# DXProMiniBoard.net
KiCad netlist of a schematic drawn in EAGLE
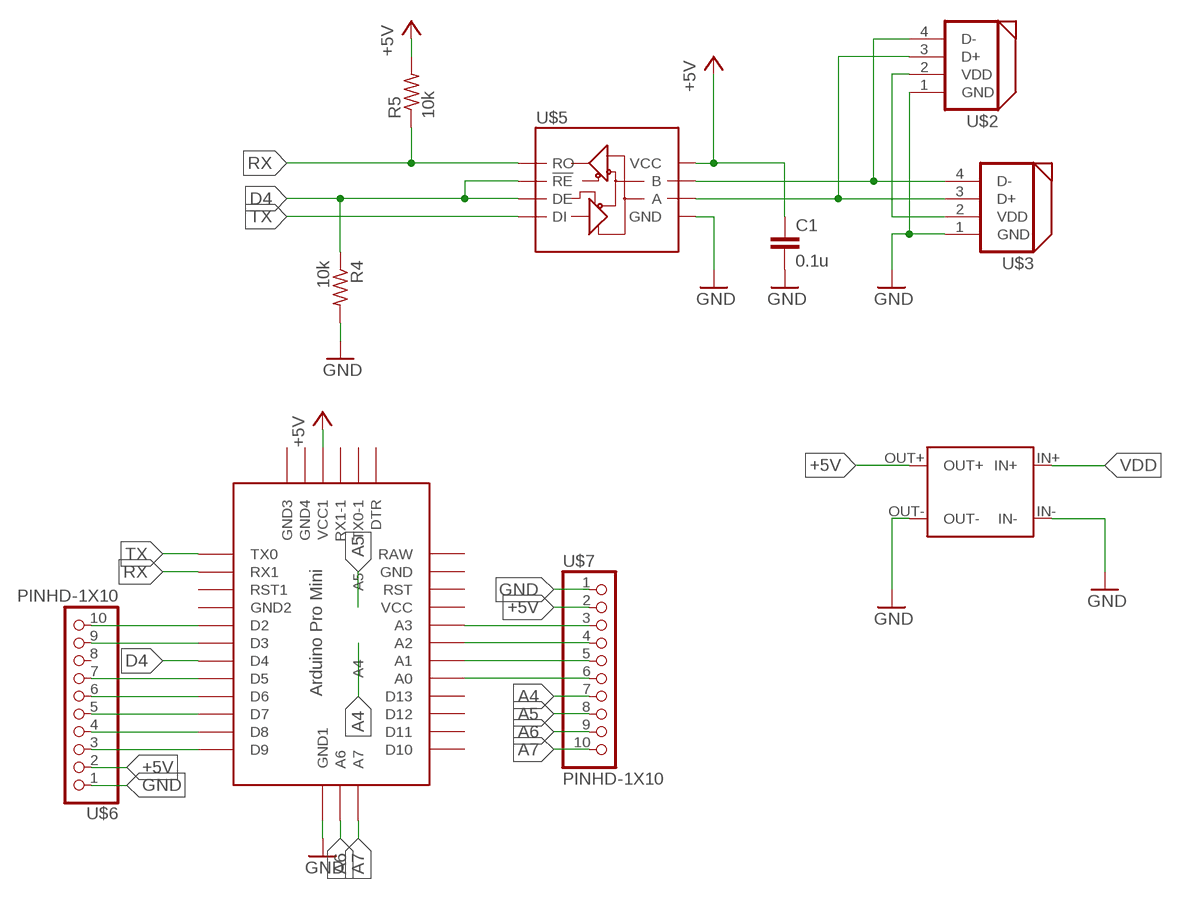
[diagram p0: schematic, sheet 1]

(export (version "E")
  (design (tool "Eeschema 10.0.6"))
  (components
    (comp (ref "C1")
      (value "0.1u")
      (footprint "eagle-import:C2.5-2")
      (libsource (lib "eagle-import") (part "C2.5/2"))
    )
    (comp (ref "R4")
      (value "10k")
      (footprint "eagle-import:0207_10")
      (libsource (lib "eagle-import") (part "R-US_0207/10"))
    )
    (comp (ref "R5")
      (value "10k")
      (footprint "eagle-import:0207_10")
      (libsource (lib "eagle-import") (part "R-US_0207/10"))
    )
    (comp (ref "U$1")
      (value "MH-MINI-360MH")
      (footprint "eagle-import:MH-MINI-360")
      (libsource (lib "eagle-import") (part "MH-MINI-360MH"))
    )
    (comp (ref "U$2")
      (value "DYNAMIXEL_RS485")
      (footprint "eagle-import:DYNAMIXEL_SPOX_04")
      (libsource (lib "eagle-import") (part "DYNAMIXEL_RS485"))
    )
    (comp (ref "U$3")
      (value "DYNAMIXEL_RS485")
      (footprint "eagle-import:DYNAMIXEL_SPOX_04")
      (libsource (lib "eagle-import") (part "DYNAMIXEL_RS485"))
    )
    (comp (ref "U$4")
      (value "ABK-PRO-MINI")
      (footprint "eagle-import:ABK-PRO-MINI")
      (libsource (lib "eagle-import") (part "ABK-PRO-MINI"))
    )
    (comp (ref "U$5")
      (value "SN75176B")
      (footprint "eagle-import:DIL08")
      (libsource (lib "eagle-import") (part "SN75176B"))
    )
    (comp (ref "U$6")
      (value "PINHD-1X10")
      (footprint "eagle-import:1X10-BIG")
      (libsource (lib "eagle-import") (part "PINHD-1X10"))
    )
    (comp (ref "U$7")
      (value "PINHD-1X10")
      (footprint "eagle-import:1X10-BIG")
      (libsource (lib "eagle-import") (part "PINHD-1X10"))
    )
  )
  (nets
    (net (code "1") (name "+5V") (class "Default")
      (node (ref "C1") (pin "1") (pinfunction "1_1") (pintype "passive"))
      (node (ref "R5") (pin "2") (pinfunction "2_2") (pintype "passive"))
      (node (ref "U$1") (pin "OUT+") (pinfunction "OUT+_OUT+") (pintype "bidirectional"))
      (node (ref "U$4") (pin "VCC1") (pinfunction "VCC1_VCC1") (pintype "bidirectional"))
      (node (ref "U$5") (pin "8") (pinfunction "VCC_8") (pintype "bidirectional"))
      (node (ref "U$6") (pin "2") (pinfunction "2_2") (pintype "passive"))
      (node (ref "U$7") (pin "2") (pinfunction "2_2") (pintype "passive"))
    )
    (net (code "2") (name "A4") (class "Default")
      (node (ref "U$4") (pin "A4") (pinfunction "A4_A4") (pintype "bidirectional"))
      (node (ref "U$7") (pin "7") (pinfunction "7_7") (pintype "passive"))
    )
    (net (code "3") (name "A5") (class "Default")
      (node (ref "U$4") (pin "A5") (pinfunction "A5_A5") (pintype "bidirectional"))
      (node (ref "U$7") (pin "8") (pinfunction "8_8") (pintype "passive"))
    )
    (net (code "4") (name "A6") (class "Default")
      (node (ref "U$4") (pin "A6") (pinfunction "A6_A6") (pintype "bidirectional"))
      (node (ref "U$7") (pin "9") (pinfunction "9_9") (pintype "passive"))
    )
    (net (code "5") (name "A7") (class "Default")
      (node (ref "U$4") (pin "A7") (pinfunction "A7_A7") (pintype "bidirectional"))
      (node (ref "U$7") (pin "10") (pinfunction "10_10") (pintype "passive"))
    )
    (net (code "6") (name "D4") (class "Default")
      (node (ref "R4") (pin "1") (pinfunction "1_1") (pintype "passive"))
      (node (ref "U$4") (pin "D4") (pinfunction "D4_D4") (pintype "bidirectional"))
      (node (ref "U$5") (pin "2") (pinfunction "~{RE}_2") (pintype "bidirectional"))
      (node (ref "U$5") (pin "3") (pinfunction "DE_3") (pintype "bidirectional"))
    )
    (net (code "7") (name "GND") (class "Default")
      (node (ref "C1") (pin "2") (pinfunction "2_2") (pintype "passive"))
      (node (ref "R4") (pin "2") (pinfunction "2_2") (pintype "passive"))
      (node (ref "U$1") (pin "IN-") (pinfunction "IN-_IN-") (pintype "bidirectional"))
      (node (ref "U$1") (pin "OUT-") (pinfunction "OUT-_OUT-") (pintype "bidirectional"))
      (node (ref "U$2") (pin "1") (pinfunction "GND_1") (pintype "power_in"))
      (node (ref "U$3") (pin "1") (pinfunction "GND_1") (pintype "power_in"))
      (node (ref "U$4") (pin "GND4") (pinfunction "GND1_GND4") (pintype "bidirectional"))
      (node (ref "U$5") (pin "5") (pinfunction "GND_5") (pintype "bidirectional"))
      (node (ref "U$6") (pin "1") (pinfunction "1_1") (pintype "passive"))
      (node (ref "U$7") (pin "1") (pinfunction "1_1") (pintype "passive"))
    )
    (net (code "8") (name "Net-(U$2-D+)") (class "Default")
      (node (ref "U$2") (pin "3") (pinfunction "D+_3") (pintype "bidirectional"))
      (node (ref "U$3") (pin "3") (pinfunction "D+_3") (pintype "bidirectional"))
      (node (ref "U$5") (pin "6") (pinfunction "A_6") (pintype "bidirectional"))
    )
    (net (code "9") (name "Net-(U$2-D-)") (class "Default")
      (node (ref "U$2") (pin "4") (pinfunction "D-_4") (pintype "bidirectional"))
      (node (ref "U$3") (pin "4") (pinfunction "D-_4") (pintype "bidirectional"))
      (node (ref "U$5") (pin "7") (pinfunction "B_7") (pintype "bidirectional"))
    )
    (net (code "10") (name "Net-(U$4-PadA0)") (class "Default")
      (node (ref "U$4") (pin "A0") (pinfunction "A0_A0") (pintype "bidirectional"))
      (node (ref "U$7") (pin "6") (pinfunction "6_6") (pintype "passive"))
    )
    (net (code "11") (name "Net-(U$4-PadA1)") (class "Default")
      (node (ref "U$4") (pin "A1") (pinfunction "A1_A1") (pintype "bidirectional"))
      (node (ref "U$7") (pin "5") (pinfunction "5_5") (pintype "passive"))
    )
    (net (code "12") (name "Net-(U$4-PadA2)") (class "Default")
      (node (ref "U$4") (pin "A2") (pinfunction "A2_A2") (pintype "bidirectional"))
      (node (ref "U$7") (pin "4") (pinfunction "4_4") (pintype "passive"))
    )
    (net (code "13") (name "Net-(U$4-PadA3)") (class "Default")
      (node (ref "U$4") (pin "A3") (pinfunction "A3_A3") (pintype "bidirectional"))
      (node (ref "U$7") (pin "3") (pinfunction "3_3") (pintype "passive"))
    )
    (net (code "14") (name "Net-(U$4-PadD2)") (class "Default")
      (node (ref "U$4") (pin "D2") (pinfunction "D2_D2") (pintype "bidirectional"))
      (node (ref "U$6") (pin "10") (pinfunction "10_10") (pintype "passive"))
    )
    (net (code "15") (name "Net-(U$4-PadD3)") (class "Default")
      (node (ref "U$4") (pin "D3") (pinfunction "D3_D3") (pintype "bidirectional"))
      (node (ref "U$6") (pin "9") (pinfunction "9_9") (pintype "passive"))
    )
    (net (code "16") (name "Net-(U$4-PadD5)") (class "Default")
      (node (ref "U$4") (pin "D5") (pinfunction "D5_D5") (pintype "bidirectional"))
      (node (ref "U$6") (pin "7") (pinfunction "7_7") (pintype "passive"))
    )
    (net (code "17") (name "Net-(U$4-PadD6)") (class "Default")
      (node (ref "U$4") (pin "D6") (pinfunction "D6_D6") (pintype "bidirectional"))
      (node (ref "U$6") (pin "6") (pinfunction "6_6") (pintype "passive"))
    )
    (net (code "18") (name "Net-(U$4-PadD7)") (class "Default")
      (node (ref "U$4") (pin "D7") (pinfunction "D7_D7") (pintype "bidirectional"))
      (node (ref "U$6") (pin "5") (pinfunction "5_5") (pintype "passive"))
    )
    (net (code "19") (name "Net-(U$4-PadD8)") (class "Default")
      (node (ref "U$4") (pin "D8") (pinfunction "D8_D8") (pintype "bidirectional"))
      (node (ref "U$6") (pin "4") (pinfunction "4_4") (pintype "passive"))
    )
    (net (code "20") (name "Net-(U$4-PadD9)") (class "Default")
      (node (ref "U$4") (pin "D9") (pinfunction "D9_D9") (pintype "bidirectional"))
      (node (ref "U$6") (pin "3") (pinfunction "3_3") (pintype "passive"))
    )
    (net (code "21") (name "RX") (class "Default")
      (node (ref "R5") (pin "1") (pinfunction "1_1") (pintype "passive"))
      (node (ref "U$4") (pin "RX1") (pinfunction "RX1_RX1") (pintype "bidirectional"))
      (node (ref "U$5") (pin "1") (pinfunction "RO_1") (pintype "bidirectional"))
    )
    (net (code "22") (name "TX") (class "Default")
      (node (ref "U$4") (pin "TX0") (pinfunction "TX0_TX0") (pintype "bidirectional"))
      (node (ref "U$5") (pin "4") (pinfunction "DI_4") (pintype "bidirectional"))
    )
    (net (code "23") (name "VDD") (class "Default")
      (node (ref "U$1") (pin "IN+") (pinfunction "IN+_IN+") (pintype "bidirectional"))
      (node (ref "U$2") (pin "2") (pinfunction "VDD_2") (pintype "power_in"))
      (node (ref "U$3") (pin "2") (pinfunction "VDD_2") (pintype "power_in"))
    )
    (net (code "24") (name "unconnected-(U$4-GND2-PadGND1)") (class "Default")
      (node (ref "U$4") (pin "GND1") (pinfunction "GND2_GND1") (pintype "bidirectional"))
    )
    (net (code "25") (name "unconnected-(U$4-GND3-PadGND2)") (class "Default")
      (node (ref "U$4") (pin "GND2") (pinfunction "GND3_GND2") (pintype "bidirectional"))
    )
    (net (code "26") (name "unconnected-(U$4-GND4-PadGND3)") (class "Default")
      (node (ref "U$4") (pin "GND3") (pinfunction "GND4_GND3") (pintype "bidirectional"))
    )
    (net (code "27") (name "unconnected-(U$4-PadD10)") (class "Default")
      (node (ref "U$4") (pin "D10") (pinfunction "D10_D10") (pintype "bidirectional"))
    )
    (net (code "28") (name "unconnected-(U$4-PadD11)") (class "Default")
      (node (ref "U$4") (pin "D11") (pinfunction "D11_D11") (pintype "bidirectional"))
    )
    (net (code "29") (name "unconnected-(U$4-PadD12)") (class "Default")
      (node (ref "U$4") (pin "D12") (pinfunction "D12_D12") (pintype "bidirectional"))
    )
    (net (code "30") (name "unconnected-(U$4-PadD13)") (class "Default")
      (node (ref "U$4") (pin "D13") (pinfunction "D13_D13") (pintype "bidirectional"))
    )
    (net (code "31") (name "unconnected-(U$4-PadDTR)") (class "Default")
      (node (ref "U$4") (pin "DTR") (pinfunction "DTR_DTR") (pintype "bidirectional"))
    )
    (net (code "32") (name "unconnected-(U$4-PadGND)") (class "Default")
      (node (ref "U$4") (pin "GND") (pinfunction "GND_GND") (pintype "bidirectional"))
    )
    (net (code "33") (name "unconnected-(U$4-PadRAW)") (class "Default")
      (node (ref "U$4") (pin "RAW") (pinfunction "RAW_RAW") (pintype "bidirectional"))
    )
    (net (code "34") (name "unconnected-(U$4-PadRST)") (class "Default")
      (node (ref "U$4") (pin "RST") (pinfunction "RST_RST") (pintype "bidirectional"))
    )
    (net (code "35") (name "unconnected-(U$4-PadRST1)") (class "Default")
      (node (ref "U$4") (pin "RST1") (pinfunction "RST1_RST1") (pintype "bidirectional"))
    )
    (net (code "36") (name "unconnected-(U$4-PadRX1-1)") (class "Default")
      (node (ref "U$4") (pin "RX1-1") (pinfunction "RX1-1_RX1-1") (pintype "bidirectional"))
    )
    (net (code "37") (name "unconnected-(U$4-PadTX0-1)") (class "Default")
      (node (ref "U$4") (pin "TX0-1") (pinfunction "TX0-1_TX0-1") (pintype "bidirectional"))
    )
    (net (code "38") (name "unconnected-(U$4-PadVCC)") (class "Default")
      (node (ref "U$4") (pin "VCC") (pinfunction "VCC_VCC") (pintype "bidirectional"))
    )
    (net (code "39") (name "unconnected-(U$6-Pad8)") (class "Default")
      (node (ref "U$6") (pin "8") (pinfunction "8_8") (pintype "passive"))
    )
  )
)
